# MCB-USI-WM-BN-BM-22-v1_0_0.net
KiCad netlist of a schematic drawn in EAGLE
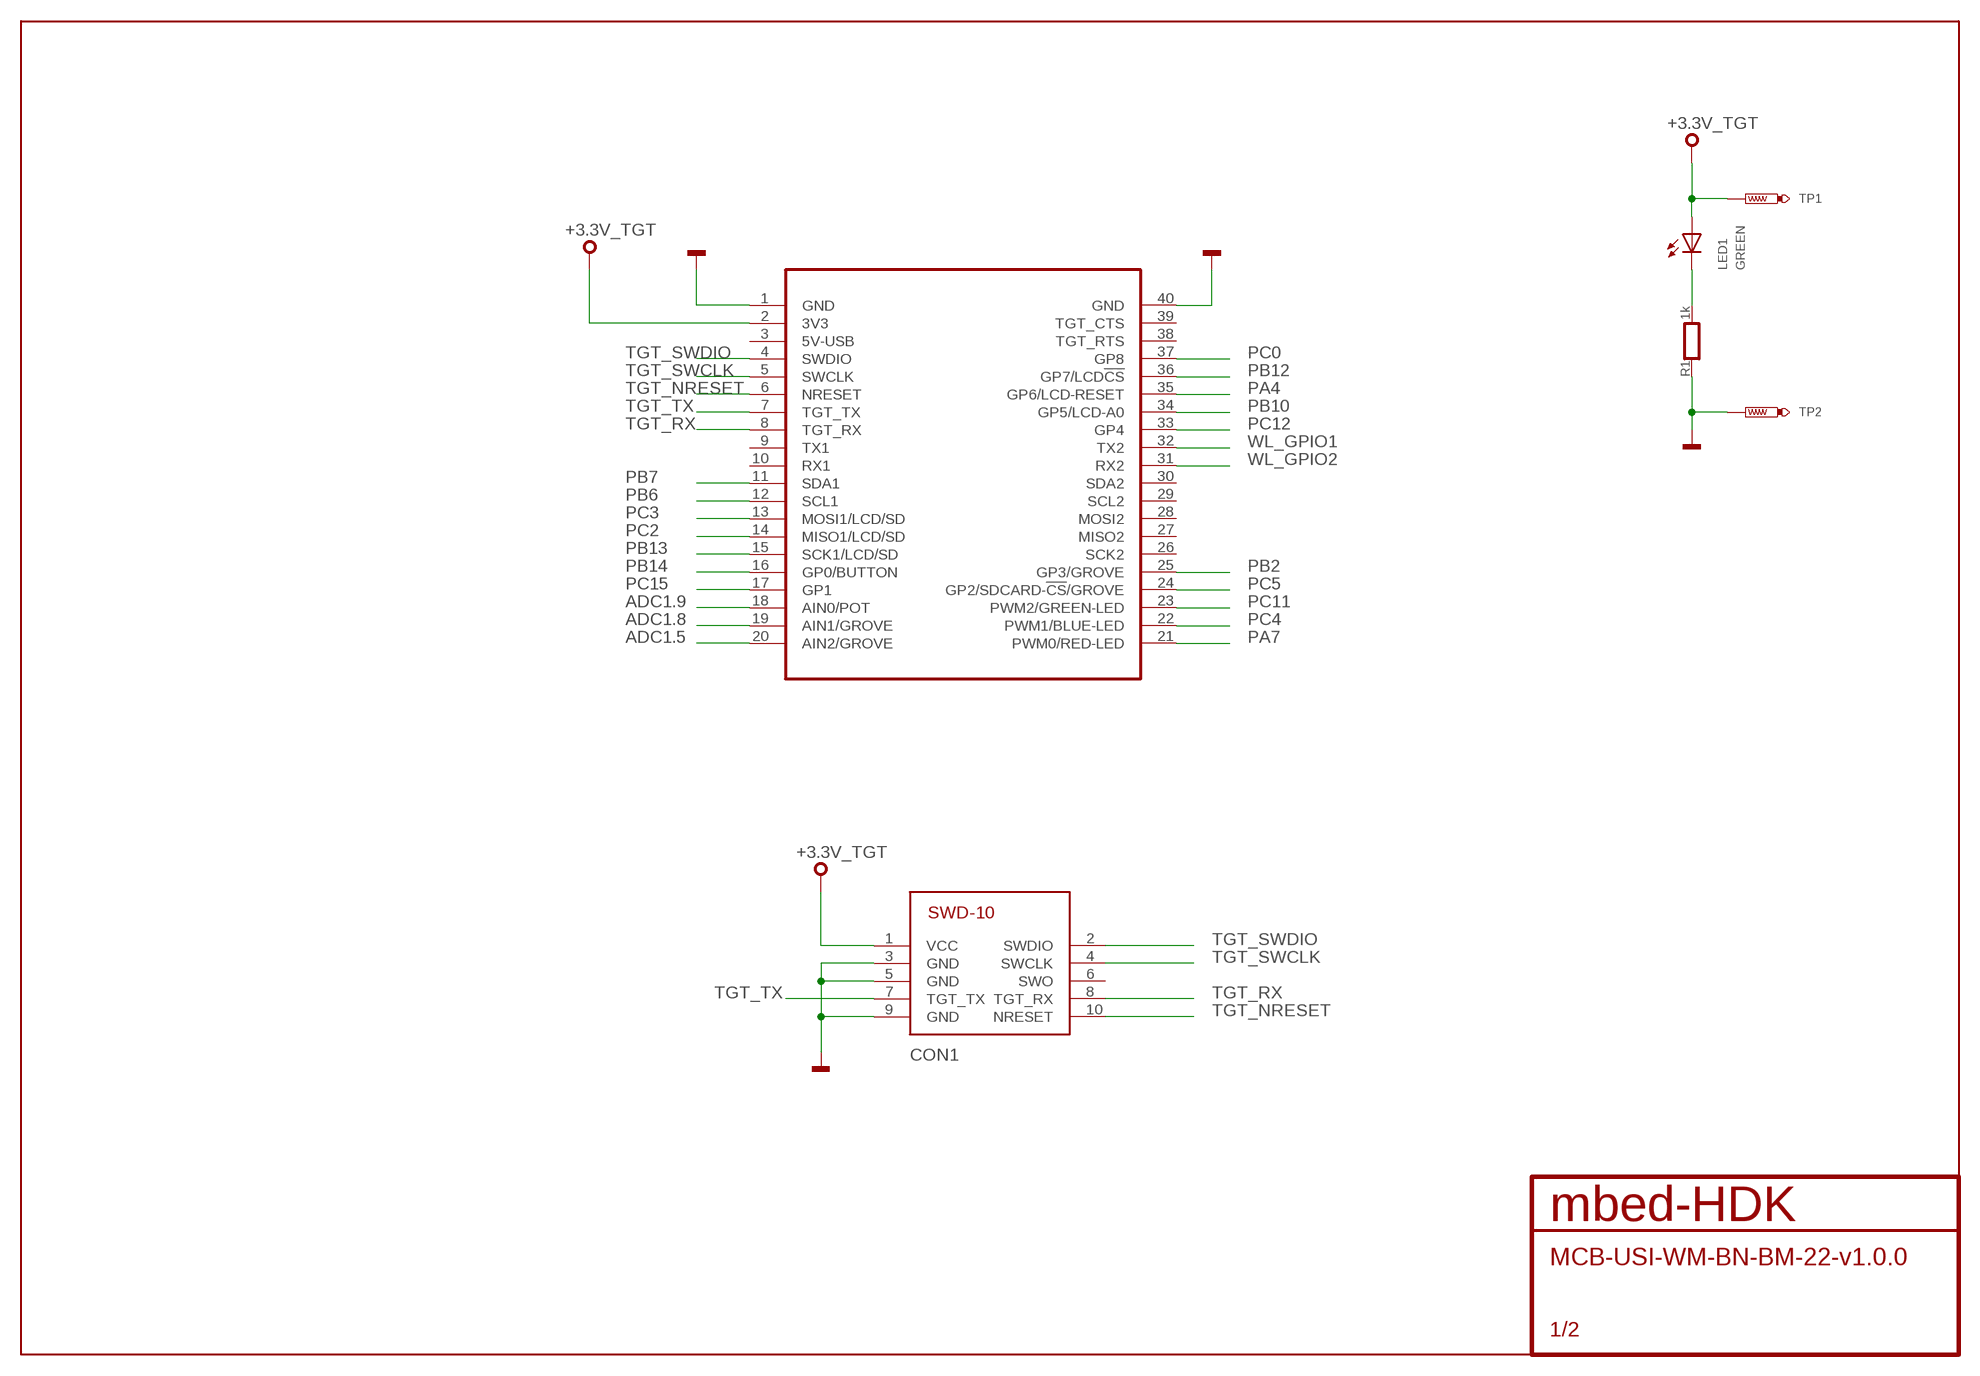
[diagram p0: schematic, sheet 1]
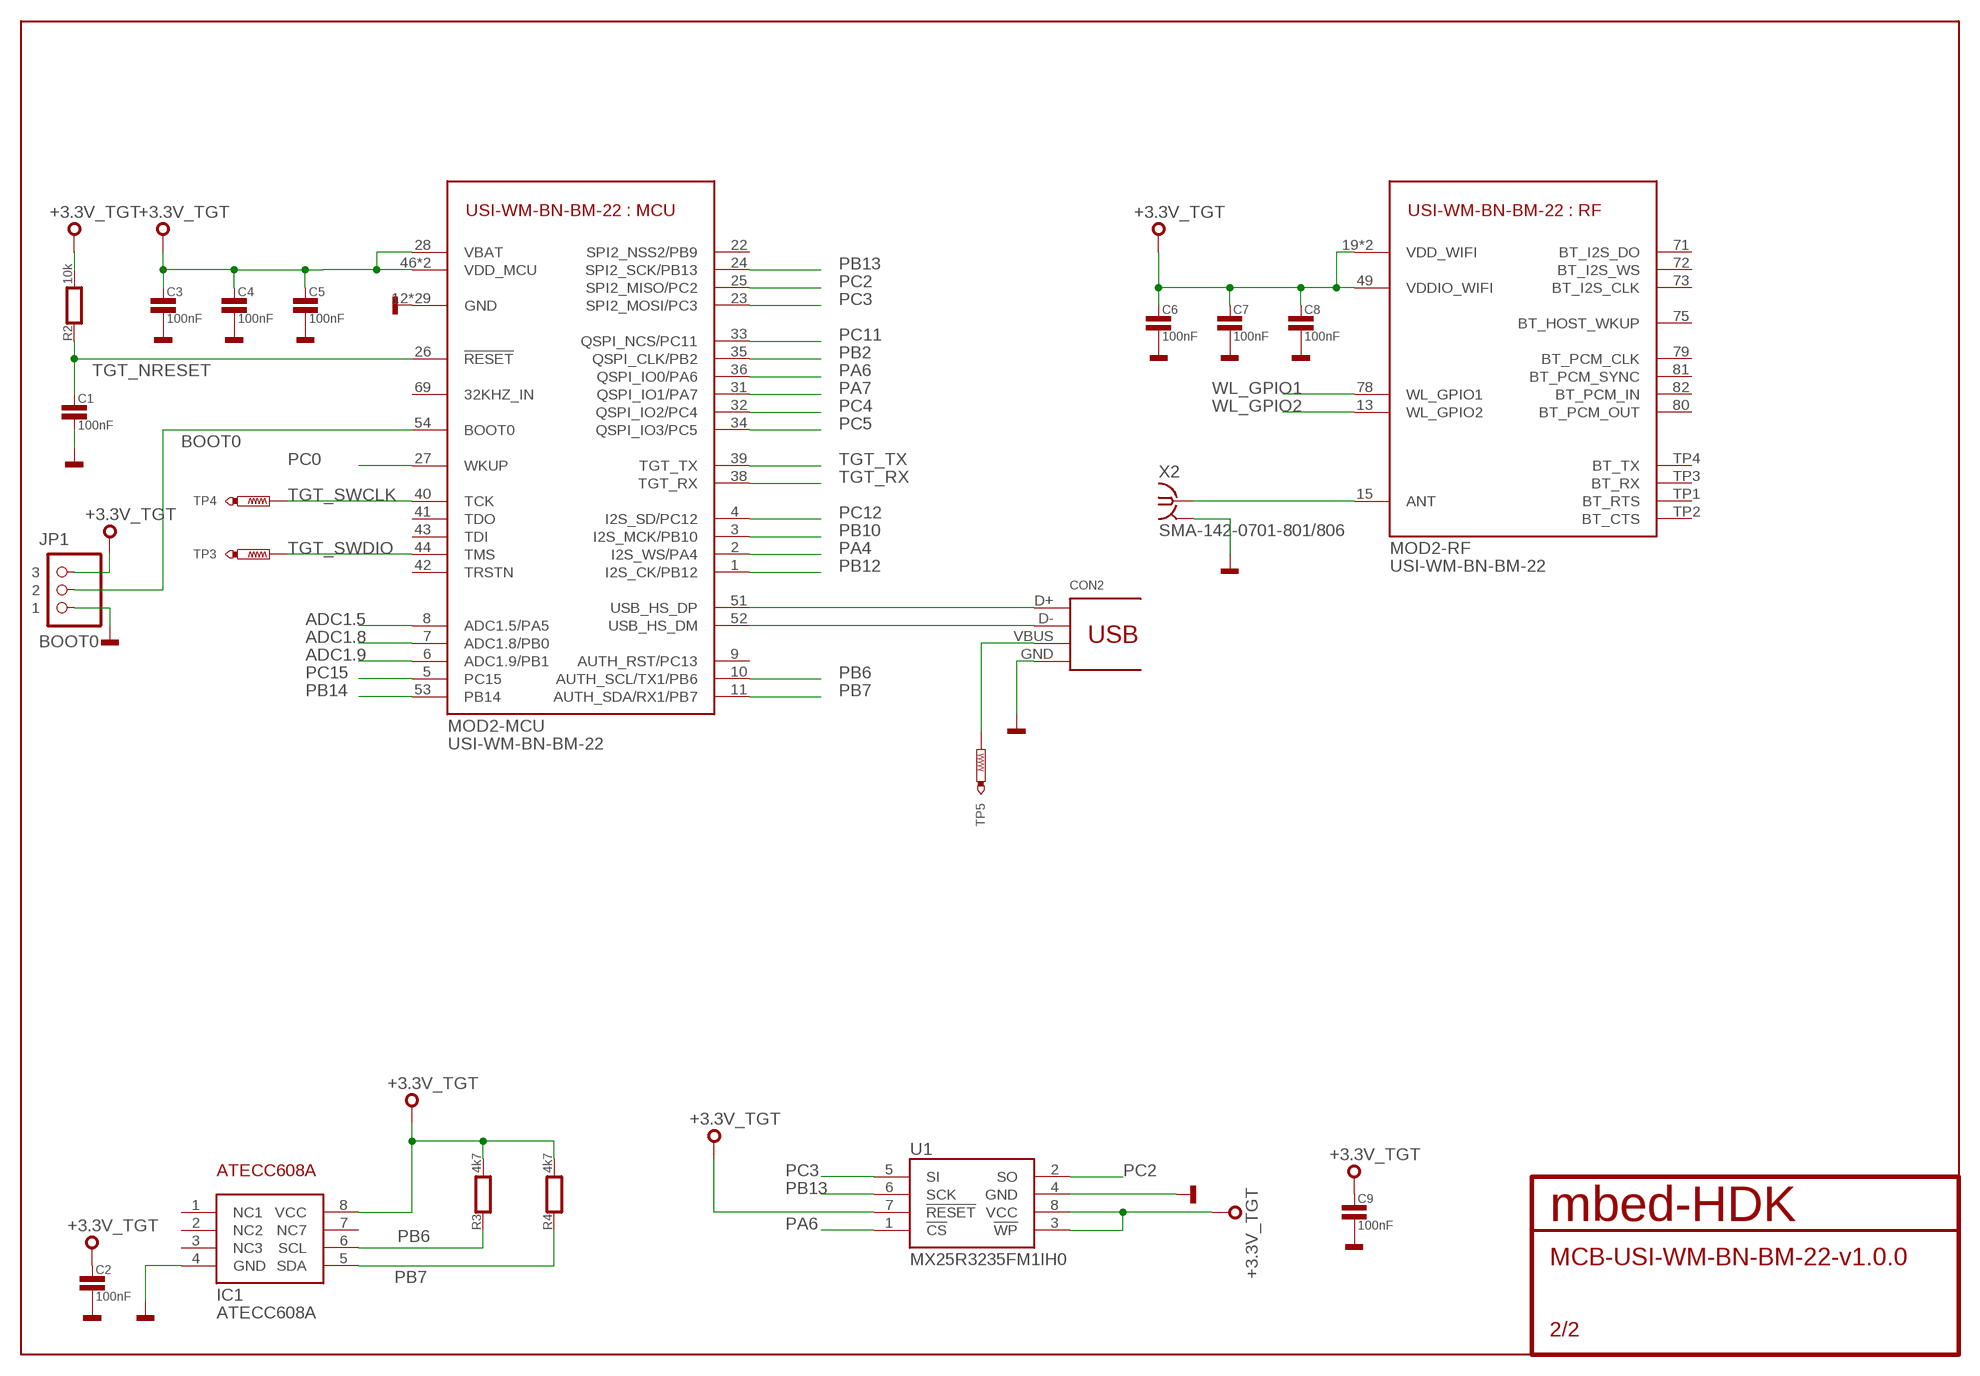
[diagram p1: schematic, sheet 2]

(export (version "E")
  (design (tool "Eeschema 10.0.6"))
  (components
    (comp (ref "CON1")
      (value "SWD-10/TC2050_SMD")
      (footprint "eagle-import:FTSH-105-02")
      (libsource (lib "eagle-import") (part "SWD-10/TC2050_SMD"))
    )
    (comp (ref "LED1")
      (value "GREEN")
      (footprint "eagle-import:CHIPLED_0603")
      (fields (field (name "MF") "Wurth Electronics Inc"))
      (libsource (lib "eagle-import") (part "SMD_LED0603"))
    )
    (comp (ref "MOD1")
      (value "MODULE_DAUGHTER")
      (footprint "eagle-import:MODULE_DAUGHTER")
      (libsource (lib "eagle-import") (part "MODULE_DAUGHTER"))
    )
    (comp (ref "R1")
      (value "1k")
      (footprint "eagle-import:0603")
      (libsource (lib "eagle-import") (part "R0603"))
    )
    (comp (ref "TP1")
      (value "TEST_POINT-50R-PTH")
      (footprint "eagle-import:TP50-PTH")
      (libsource (lib "eagle-import") (part "TEST_POINT-50R-PTH"))
    )
    (comp (ref "TP2")
      (value "TEST_POINT-50R-PTH")
      (footprint "eagle-import:TP50-PTH")
      (libsource (lib "eagle-import") (part "TEST_POINT-50R-PTH"))
    )
    (comp (ref "C1")
      (value "100nF")
      (footprint "eagle-import:0603")
      (libsource (lib "eagle-import") (part "C0603"))
    )
    (comp (ref "C2")
      (value "100nF")
      (footprint "eagle-import:0603")
      (libsource (lib "eagle-import") (part "C0603"))
    )
    (comp (ref "C3")
      (value "100nF")
      (footprint "eagle-import:0603")
      (libsource (lib "eagle-import") (part "C0603"))
    )
    (comp (ref "C4")
      (value "100nF")
      (footprint "eagle-import:0603")
      (libsource (lib "eagle-import") (part "C0603"))
    )
    (comp (ref "C5")
      (value "100nF")
      (footprint "eagle-import:0603")
      (libsource (lib "eagle-import") (part "C0603"))
    )
    (comp (ref "C6")
      (value "100nF")
      (footprint "eagle-import:0603")
      (libsource (lib "eagle-import") (part "C0603"))
    )
    (comp (ref "C7")
      (value "100nF")
      (footprint "eagle-import:0603")
      (libsource (lib "eagle-import") (part "C0603"))
    )
    (comp (ref "C8")
      (value "100nF")
      (footprint "eagle-import:0603")
      (libsource (lib "eagle-import") (part "C0603"))
    )
    (comp (ref "C9")
      (value "100nF")
      (footprint "eagle-import:0603")
      (libsource (lib "eagle-import") (part "C0603"))
    )
    (comp (ref "CON2")
      (value "47346-0001")
      (footprint "eagle-import:USB-MICRO-B-H")
      (fields (field (name "MF") "MOLEX"))
      (libsource (lib "eagle-import") (part "47346-0001"))
    )
    (comp (ref "IC1")
      (value "ATECC608A")
      (footprint "eagle-import:SO8")
      (fields (field (name "MF") "Atmel"))
      (libsource (lib "eagle-import") (part "ATECC608A"))
    )
    (comp (ref "JP1")
      (value "BOOT0")
      (footprint "eagle-import:1X03")
      (libsource (lib "eagle-import") (part "PINHD-1X3"))
    )
    (comp (ref "MOD2")
      (value "USI-WM-BN-BM-22")
      (footprint "eagle-import:USI-WM-BN-BM-22")
      (libsource (lib "eagle-import") (part "USI-WM-BN-BM-22"))
    )
    (comp (ref "R2")
      (value "10k")
      (footprint "eagle-import:0603")
      (libsource (lib "eagle-import") (part "R0603"))
    )
    (comp (ref "R3")
      (value "4k7")
      (footprint "eagle-import:0603")
      (libsource (lib "eagle-import") (part "R0603"))
    )
    (comp (ref "R4")
      (value "4k7")
      (footprint "eagle-import:0603")
      (libsource (lib "eagle-import") (part "R0603"))
    )
    (comp (ref "TP3")
      (value "TEST_POINT-50R-SMD")
      (footprint "eagle-import:TP50-SMD")
      (libsource (lib "eagle-import") (part "TEST_POINT-50R-SMD"))
    )
    (comp (ref "TP4")
      (value "TEST_POINT-50R-SMD")
      (footprint "eagle-import:TP50-SMD")
      (libsource (lib "eagle-import") (part "TEST_POINT-50R-SMD"))
    )
    (comp (ref "TP5")
      (value "TEST_POINT-50R-SMD")
      (footprint "eagle-import:TP50-SMD")
      (libsource (lib "eagle-import") (part "TEST_POINT-50R-SMD"))
    )
    (comp (ref "U1")
      (value "MX25R3235FM1IH0")
      (footprint "eagle-import:SO8")
      (fields (field (name "MF") "Macronix"))
      (libsource (lib "eagle-import") (part "MX25R3235FM1IH0"))
    )
    (comp (ref "X2")
      (value "SMA-142-0701-801/806")
      (footprint "eagle-import:J502-ND-142-0701-801_806")
      (fields (field (name "MF") "JOHNSON COMPONENTS") (field (name "MPN") "142-0701-801"))
      (libsource (lib "eagle-import") (part "SMA-142-0701-801/806"))
    )
  )
  (nets
    (net (code "1") (name "+3.3V_TGT") (class "Default")
      (node (ref "C2") (pin "1") (pinfunction "P$1_1") (pintype "passive"))
      (node (ref "C3") (pin "1") (pinfunction "P$1_1") (pintype "passive"))
      (node (ref "C4") (pin "1") (pinfunction "P$1_1") (pintype "passive"))
      (node (ref "C5") (pin "1") (pinfunction "P$1_1") (pintype "passive"))
      (node (ref "C6") (pin "1") (pinfunction "P$1_1") (pintype "passive"))
      (node (ref "C7") (pin "1") (pinfunction "P$1_1") (pintype "passive"))
      (node (ref "C8") (pin "1") (pinfunction "P$1_1") (pintype "passive"))
      (node (ref "C9") (pin "1") (pinfunction "P$1_1") (pintype "passive"))
      (node (ref "CON1") (pin "1") (pinfunction "VCC_1") (pintype "bidirectional"))
      (node (ref "IC1") (pin "8") (pinfunction "VCC_8") (pintype "bidirectional"))
      (node (ref "JP1") (pin "3") (pinfunction "3_3") (pintype "passive"))
      (node (ref "LED1") (pin "A") (pinfunction "A_A") (pintype "passive"))
      (node (ref "MOD1") (pin "2") (pinfunction "3V3_2") (pintype "bidirectional"))
      (node (ref "MOD2") (pin "19") (pinfunction "VDD_WIFI_19") (pintype "bidirectional"))
      (node (ref "MOD2") (pin "20") (pinfunction "VDD_WIFI_20") (pintype "bidirectional"))
      (node (ref "MOD2") (pin "28") (pinfunction "VBAT_28") (pintype "bidirectional"))
      (node (ref "MOD2") (pin "46") (pinfunction "VDD_MCU_46") (pintype "bidirectional"))
      (node (ref "MOD2") (pin "47") (pinfunction "VDD_MCU_47") (pintype "bidirectional"))
      (node (ref "MOD2") (pin "49") (pinfunction "VDDIO_WIFI_49") (pintype "bidirectional"))
      (node (ref "R2") (pin "2") (pinfunction "P$2_2") (pintype "passive"))
      (node (ref "R3") (pin "2") (pinfunction "P$2_2") (pintype "passive"))
      (node (ref "R4") (pin "2") (pinfunction "P$2_2") (pintype "passive"))
      (node (ref "TP1") (pin "TP") (pinfunction "TP_TP") (pintype "input"))
      (node (ref "U1") (pin "3") (pinfunction "~{WP}_3") (pintype "bidirectional"))
      (node (ref "U1") (pin "7") (pinfunction "~{RESET}_7") (pintype "bidirectional"))
      (node (ref "U1") (pin "8") (pinfunction "VCC_8") (pintype "bidirectional"))
    )
    (net (code "2") (name "ADC1.5") (class "Default")
      (node (ref "MOD1") (pin "20") (pinfunction "AIN2/GROVE_20") (pintype "bidirectional"))
      (node (ref "MOD2") (pin "8") (pinfunction "ADC1.5/PA5_8") (pintype "bidirectional"))
    )
    (net (code "3") (name "ADC1.8") (class "Default")
      (node (ref "MOD1") (pin "19") (pinfunction "AIN1/GROVE_19") (pintype "bidirectional"))
      (node (ref "MOD2") (pin "7") (pinfunction "ADC1.8/PB0_7") (pintype "bidirectional"))
    )
    (net (code "4") (name "ADC1.9") (class "Default")
      (node (ref "MOD1") (pin "18") (pinfunction "AIN0/POT_18") (pintype "bidirectional"))
      (node (ref "MOD2") (pin "6") (pinfunction "ADC1.9/PB1_6") (pintype "bidirectional"))
    )
    (net (code "5") (name "BOOT0") (class "Default")
      (node (ref "JP1") (pin "2") (pinfunction "2_2") (pintype "passive"))
      (node (ref "MOD2") (pin "54") (pinfunction "BOOT0_54") (pintype "bidirectional"))
    )
    (net (code "6") (name "GND") (class "Default")
      (node (ref "C1") (pin "2") (pinfunction "P$2_2") (pintype "passive"))
      (node (ref "C2") (pin "2") (pinfunction "P$2_2") (pintype "passive"))
      (node (ref "C3") (pin "2") (pinfunction "P$2_2") (pintype "passive"))
      (node (ref "C4") (pin "2") (pinfunction "P$2_2") (pintype "passive"))
      (node (ref "C5") (pin "2") (pinfunction "P$2_2") (pintype "passive"))
      (node (ref "C6") (pin "2") (pinfunction "P$2_2") (pintype "passive"))
      (node (ref "C7") (pin "2") (pinfunction "P$2_2") (pintype "passive"))
      (node (ref "C8") (pin "2") (pinfunction "P$2_2") (pintype "passive"))
      (node (ref "C9") (pin "2") (pinfunction "P$2_2") (pintype "passive"))
      (node (ref "CON1") (pin "3") (pinfunction "GND_3") (pintype "bidirectional"))
      (node (ref "CON1") (pin "5") (pinfunction "GND_5") (pintype "bidirectional"))
      (node (ref "CON1") (pin "9") (pinfunction "GND_9") (pintype "bidirectional"))
      (node (ref "CON2") (pin "GND") (pinfunction "GND_GND") (pintype "bidirectional"))
      (node (ref "IC1") (pin "4") (pinfunction "GND_4") (pintype "bidirectional"))
      (node (ref "JP1") (pin "1") (pinfunction "1_1") (pintype "passive"))
      (node (ref "MOD1") (pin "1") (pinfunction "GND_1") (pintype "bidirectional"))
      (node (ref "MOD1") (pin "40") (pinfunction "GND_40") (pintype "bidirectional"))
      (node (ref "MOD2") (pin "12") (pinfunction "GND_12") (pintype "bidirectional"))
      (node (ref "MOD2") (pin "14") (pinfunction "GND_14") (pintype "bidirectional"))
      (node (ref "MOD2") (pin "16") (pinfunction "GND_16") (pintype "bidirectional"))
      (node (ref "MOD2") (pin "17") (pinfunction "GND_17") (pintype "bidirectional"))
      (node (ref "MOD2") (pin "18") (pinfunction "GND_18") (pintype "bidirectional"))
      (node (ref "MOD2") (pin "21") (pinfunction "GND_21") (pintype "bidirectional"))
      (node (ref "MOD2") (pin "29") (pinfunction "GND_29") (pintype "bidirectional"))
      (node (ref "MOD2") (pin "30") (pinfunction "GND_30") (pintype "bidirectional"))
      (node (ref "MOD2") (pin "37") (pinfunction "GND_37") (pintype "bidirectional"))
      (node (ref "MOD2") (pin "45") (pinfunction "GND_45") (pintype "bidirectional"))
      (node (ref "MOD2") (pin "48") (pinfunction "GND_48") (pintype "bidirectional"))
      (node (ref "MOD2") (pin "50") (pinfunction "GND_50") (pintype "bidirectional"))
      (node (ref "MOD2") (pin "55") (pinfunction "GND_55") (pintype "bidirectional"))
      (node (ref "MOD2") (pin "56") (pinfunction "GND_56") (pintype "bidirectional"))
      (node (ref "MOD2") (pin "57") (pinfunction "GND_57") (pintype "bidirectional"))
      (node (ref "MOD2") (pin "58") (pinfunction "GND_58") (pintype "bidirectional"))
      (node (ref "MOD2") (pin "59") (pinfunction "GND_59") (pintype "bidirectional"))
      (node (ref "MOD2") (pin "60") (pinfunction "GND_60") (pintype "bidirectional"))
      (node (ref "MOD2") (pin "61") (pinfunction "GND_61") (pintype "bidirectional"))
      (node (ref "MOD2") (pin "62") (pinfunction "GND_62") (pintype "bidirectional"))
      (node (ref "MOD2") (pin "63") (pinfunction "GND_63") (pintype "bidirectional"))
      (node (ref "MOD2") (pin "64") (pinfunction "GND_64") (pintype "bidirectional"))
      (node (ref "MOD2") (pin "65") (pinfunction "GND_65") (pintype "bidirectional"))
      (node (ref "MOD2") (pin "66") (pinfunction "GND_66") (pintype "bidirectional"))
      (node (ref "MOD2") (pin "67") (pinfunction "GND_67") (pintype "bidirectional"))
      (node (ref "MOD2") (pin "68") (pinfunction "GND_68") (pintype "bidirectional"))
      (node (ref "MOD2") (pin "70") (pinfunction "GND_70") (pintype "bidirectional"))
      (node (ref "MOD2") (pin "74") (pinfunction "GND_74") (pintype "bidirectional"))
      (node (ref "MOD2") (pin "83") (pinfunction "GND_83") (pintype "bidirectional"))
      (node (ref "R1") (pin "1") (pinfunction "P$1_1") (pintype "passive"))
      (node (ref "TP2") (pin "TP") (pinfunction "TP_TP") (pintype "input"))
      (node (ref "U1") (pin "4") (pinfunction "GND_4") (pintype "bidirectional"))
      (node (ref "X2") (pin "G@1") (pinfunction "2_G@1") (pintype "passive"))
      (node (ref "X2") (pin "G@2") (pinfunction "2_G@2") (pintype "passive"))
      (node (ref "X2") (pin "G@3") (pinfunction "2_G@3") (pintype "passive"))
      (node (ref "X2") (pin "G@4") (pinfunction "2_G@4") (pintype "passive"))
    )
    (net (code "7") (name "Net-(CON2-PadVBUS)") (class "Default")
      (node (ref "CON2") (pin "VBUS") (pinfunction "VBUS_VBUS") (pintype "bidirectional"))
      (node (ref "TP5") (pin "TP") (pinfunction "TP_TP") (pintype "input"))
    )
    (net (code "8") (name "Net-(MOD2A-USB_HS_DM)") (class "Default")
      (node (ref "CON2") (pin "D-") (pinfunction "D-_D-") (pintype "bidirectional"))
      (node (ref "MOD2") (pin "52") (pinfunction "USB_HS_DM_52") (pintype "bidirectional"))
    )
    (net (code "9") (name "Net-(MOD2A-USB_HS_DP)") (class "Default")
      (node (ref "CON2") (pin "D+") (pinfunction "D+_D+") (pintype "bidirectional"))
      (node (ref "MOD2") (pin "51") (pinfunction "USB_HS_DP_51") (pintype "bidirectional"))
    )
    (net (code "10") (name "Net-(MOD2B-ANT)") (class "Default")
      (node (ref "MOD2") (pin "15") (pinfunction "ANT_15") (pintype "bidirectional"))
      (node (ref "X2") (pin "1") (pinfunction "1_1") (pintype "passive"))
    )
    (net (code "11") (name "Net-(R1-P$2)") (class "Default")
      (node (ref "LED1") (pin "C") (pinfunction "C_C") (pintype "passive"))
      (node (ref "R1") (pin "2") (pinfunction "P$2_2") (pintype "passive"))
    )
    (net (code "12") (name "PA4") (class "Default")
      (node (ref "MOD1") (pin "35") (pinfunction "GP6/LCD-RESET_35") (pintype "bidirectional"))
      (node (ref "MOD2") (pin "2") (pinfunction "I2S_WS/PA4_2") (pintype "bidirectional"))
    )
    (net (code "13") (name "PA6") (class "Default")
      (node (ref "MOD2") (pin "36") (pinfunction "QSPI_IO0/PA6_36") (pintype "bidirectional"))
      (node (ref "U1") (pin "1") (pinfunction "~{CS}_1") (pintype "bidirectional"))
    )
    (net (code "14") (name "PA7") (class "Default")
      (node (ref "MOD1") (pin "21") (pinfunction "PWM0/RED-LED_21") (pintype "bidirectional"))
      (node (ref "MOD2") (pin "31") (pinfunction "QSPI_IO1/PA7_31") (pintype "bidirectional"))
    )
    (net (code "15") (name "PB2") (class "Default")
      (node (ref "MOD1") (pin "25") (pinfunction "GP3/GROVE_25") (pintype "bidirectional"))
      (node (ref "MOD2") (pin "35") (pinfunction "QSPI_CLK/PB2_35") (pintype "bidirectional"))
    )
    (net (code "16") (name "PB6") (class "Default")
      (node (ref "IC1") (pin "6") (pinfunction "SCL_6") (pintype "bidirectional"))
      (node (ref "MOD1") (pin "12") (pinfunction "SCL1_12") (pintype "bidirectional"))
      (node (ref "MOD2") (pin "10") (pinfunction "AUTH_SCL/TX1/PB6_10") (pintype "bidirectional"))
      (node (ref "R3") (pin "1") (pinfunction "P$1_1") (pintype "passive"))
    )
    (net (code "17") (name "PB7") (class "Default")
      (node (ref "IC1") (pin "5") (pinfunction "SDA_5") (pintype "bidirectional"))
      (node (ref "MOD1") (pin "11") (pinfunction "SDA1_11") (pintype "bidirectional"))
      (node (ref "MOD2") (pin "11") (pinfunction "AUTH_SDA/RX1/PB7_11") (pintype "bidirectional"))
      (node (ref "R4") (pin "1") (pinfunction "P$1_1") (pintype "passive"))
    )
    (net (code "18") (name "PB10") (class "Default")
      (node (ref "MOD1") (pin "34") (pinfunction "GP5/LCD-A0_34") (pintype "bidirectional"))
      (node (ref "MOD2") (pin "3") (pinfunction "I2S_MCK/PB10_3") (pintype "bidirectional"))
    )
    (net (code "19") (name "PB12") (class "Default")
      (node (ref "MOD1") (pin "36") (pinfunction "GP7/LCD~{CS}_36") (pintype "bidirectional"))
      (node (ref "MOD2") (pin "1") (pinfunction "I2S_CK/PB12_1") (pintype "bidirectional"))
    )
    (net (code "20") (name "PB13") (class "Default")
      (node (ref "MOD1") (pin "15") (pinfunction "SCK1/LCD/SD_15") (pintype "bidirectional"))
      (node (ref "MOD2") (pin "24") (pinfunction "SPI2_SCK/PB13_24") (pintype "bidirectional"))
      (node (ref "U1") (pin "6") (pinfunction "SCK_6") (pintype "bidirectional"))
    )
    (net (code "21") (name "PB14") (class "Default")
      (node (ref "MOD1") (pin "16") (pinfunction "GP0/BUTTON_16") (pintype "bidirectional"))
      (node (ref "MOD2") (pin "53") (pinfunction "PB14_53") (pintype "bidirectional"))
    )
    (net (code "22") (name "PC0") (class "Default")
      (node (ref "MOD1") (pin "37") (pinfunction "GP8_37") (pintype "bidirectional"))
      (node (ref "MOD2") (pin "27") (pinfunction "WKUP_27") (pintype "bidirectional"))
    )
    (net (code "23") (name "PC2") (class "Default")
      (node (ref "MOD1") (pin "14") (pinfunction "MISO1/LCD/SD_14") (pintype "bidirectional"))
      (node (ref "MOD2") (pin "25") (pinfunction "SPI2_MISO/PC2_25") (pintype "bidirectional"))
      (node (ref "U1") (pin "2") (pinfunction "SO_2") (pintype "bidirectional"))
    )
    (net (code "24") (name "PC3") (class "Default")
      (node (ref "MOD1") (pin "13") (pinfunction "MOSI1/LCD/SD_13") (pintype "bidirectional"))
      (node (ref "MOD2") (pin "23") (pinfunction "SPI2_MOSI/PC3_23") (pintype "bidirectional"))
      (node (ref "U1") (pin "5") (pinfunction "SI_5") (pintype "bidirectional"))
    )
    (net (code "25") (name "PC4") (class "Default")
      (node (ref "MOD1") (pin "22") (pinfunction "PWM1/BLUE-LED_22") (pintype "bidirectional"))
      (node (ref "MOD2") (pin "32") (pinfunction "QSPI_IO2/PC4_32") (pintype "bidirectional"))
    )
    (net (code "26") (name "PC5") (class "Default")
      (node (ref "MOD1") (pin "24") (pinfunction "GP2/SDCARD-~{CS}/GROVE_24") (pintype "bidirectional"))
      (node (ref "MOD2") (pin "34") (pinfunction "QSPI_IO3/PC5_34") (pintype "bidirectional"))
    )
    (net (code "27") (name "PC11") (class "Default")
      (node (ref "MOD1") (pin "23") (pinfunction "PWM2/GREEN-LED_23") (pintype "bidirectional"))
      (node (ref "MOD2") (pin "33") (pinfunction "QSPI_NCS/PC11_33") (pintype "bidirectional"))
    )
    (net (code "28") (name "PC12") (class "Default")
      (node (ref "MOD1") (pin "33") (pinfunction "GP4_33") (pintype "bidirectional"))
      (node (ref "MOD2") (pin "4") (pinfunction "I2S_SD/PC12_4") (pintype "bidirectional"))
    )
    (net (code "29") (name "PC15") (class "Default")
      (node (ref "MOD1") (pin "17") (pinfunction "GP1_17") (pintype "bidirectional"))
      (node (ref "MOD2") (pin "5") (pinfunction "PC15_5") (pintype "bidirectional"))
    )
    (net (code "30") (name "TGT_NRESET") (class "Default")
      (node (ref "C1") (pin "1") (pinfunction "P$1_1") (pintype "passive"))
      (node (ref "CON1") (pin "10") (pinfunction "NRESET_10") (pintype "bidirectional"))
      (node (ref "MOD1") (pin "6") (pinfunction "NRESET_6") (pintype "bidirectional"))
      (node (ref "MOD2") (pin "26") (pinfunction "~{RESET}_26") (pintype "bidirectional"))
      (node (ref "R2") (pin "1") (pinfunction "P$1_1") (pintype "passive"))
    )
    (net (code "31") (name "TGT_RX") (class "Default")
      (node (ref "CON1") (pin "8") (pinfunction "TGT_RX_8") (pintype "bidirectional"))
      (node (ref "MOD1") (pin "8") (pinfunction "TGT_RX_8") (pintype "bidirectional"))
      (node (ref "MOD2") (pin "38") (pinfunction "TGT_RX_38") (pintype "bidirectional"))
    )
    (net (code "32") (name "TGT_SWCLK") (class "Default")
      (node (ref "CON1") (pin "4") (pinfunction "SWCLK_4") (pintype "bidirectional"))
      (node (ref "MOD1") (pin "5") (pinfunction "SWCLK_5") (pintype "bidirectional"))
      (node (ref "MOD2") (pin "40") (pinfunction "TCK_40") (pintype "bidirectional"))
      (node (ref "TP4") (pin "TP") (pinfunction "TP_TP") (pintype "input"))
    )
    (net (code "33") (name "TGT_SWDIO") (class "Default")
      (node (ref "CON1") (pin "2") (pinfunction "SWDIO_2") (pintype "bidirectional"))
      (node (ref "MOD1") (pin "4") (pinfunction "SWDIO_4") (pintype "bidirectional"))
      (node (ref "MOD2") (pin "44") (pinfunction "TMS_44") (pintype "bidirectional"))
      (node (ref "TP3") (pin "TP") (pinfunction "TP_TP") (pintype "input"))
    )
    (net (code "34") (name "TGT_TX") (class "Default")
      (node (ref "CON1") (pin "7") (pinfunction "TGT_TX_7") (pintype "bidirectional"))
      (node (ref "MOD1") (pin "7") (pinfunction "TGT_TX_7") (pintype "bidirectional"))
      (node (ref "MOD2") (pin "39") (pinfunction "TGT_TX_39") (pintype "bidirectional"))
    )
    (net (code "35") (name "WL_GPIO1") (class "Default")
      (node (ref "MOD1") (pin "32") (pinfunction "TX2_32") (pintype "bidirectional"))
      (node (ref "MOD2") (pin "78") (pinfunction "WL_GPIO1_78") (pintype "bidirectional"))
    )
    (net (code "36") (name "WL_GPIO2") (class "Default")
      (node (ref "MOD1") (pin "31") (pinfunction "RX2_31") (pintype "bidirectional"))
      (node (ref "MOD2") (pin "13") (pinfunction "WL_GPIO2_13") (pintype "bidirectional"))
    )
    (net (code "37") (name "unconnected-(CON1-SWO-Pad6)") (class "Default")
      (node (ref "CON1") (pin "6") (pinfunction "SWO_6") (pintype "bidirectional"))
    )
    (net (code "38") (name "unconnected-(IC1-NC1-Pad1)") (class "Default")
      (node (ref "IC1") (pin "1") (pinfunction "NC1_1") (pintype "bidirectional"))
    )
    (net (code "39") (name "unconnected-(IC1-NC2-Pad2)") (class "Default")
      (node (ref "IC1") (pin "2") (pinfunction "NC2_2") (pintype "bidirectional"))
    )
    (net (code "40") (name "unconnected-(IC1-NC3-Pad3)") (class "Default")
      (node (ref "IC1") (pin "3") (pinfunction "NC3_3") (pintype "bidirectional"))
    )
    (net (code "41") (name "unconnected-(IC1-NC7-Pad7)") (class "Default")
      (node (ref "IC1") (pin "7") (pinfunction "NC7_7") (pintype "bidirectional"))
    )
    (net (code "42") (name "unconnected-(MOD1-5V-USB-Pad3)") (class "Default")
      (node (ref "MOD1") (pin "3") (pinfunction "5V-USB_3") (pintype "bidirectional"))
    )
    (net (code "43") (name "unconnected-(MOD1-MISO2-Pad27)") (class "Default")
      (node (ref "MOD1") (pin "27") (pinfunction "MISO2_27") (pintype "bidirectional"))
    )
    (net (code "44") (name "unconnected-(MOD1-MOSI2-Pad28)") (class "Default")
      (node (ref "MOD1") (pin "28") (pinfunction "MOSI2_28") (pintype "bidirectional"))
    )
    (net (code "45") (name "unconnected-(MOD1-RX1-Pad10)") (class "Default")
      (node (ref "MOD1") (pin "10") (pinfunction "RX1_10") (pintype "bidirectional"))
    )
    (net (code "46") (name "unconnected-(MOD1-SCK2-Pad26)") (class "Default")
      (node (ref "MOD1") (pin "26") (pinfunction "SCK2_26") (pintype "bidirectional"))
    )
    (net (code "47") (name "unconnected-(MOD1-SCL2-Pad29)") (class "Default")
      (node (ref "MOD1") (pin "29") (pinfunction "SCL2_29") (pintype "bidirectional"))
    )
    (net (code "48") (name "unconnected-(MOD1-SDA2-Pad30)") (class "Default")
      (node (ref "MOD1") (pin "30") (pinfunction "SDA2_30") (pintype "bidirectional"))
    )
    (net (code "49") (name "unconnected-(MOD1-TGT_CTS-Pad39)") (class "Default")
      (node (ref "MOD1") (pin "39") (pinfunction "TGT_CTS_39") (pintype "bidirectional"))
    )
    (net (code "50") (name "unconnected-(MOD1-TGT_RTS-Pad38)") (class "Default")
      (node (ref "MOD1") (pin "38") (pinfunction "TGT_RTS_38") (pintype "bidirectional"))
    )
    (net (code "51") (name "unconnected-(MOD1-TX1-Pad9)") (class "Default")
      (node (ref "MOD1") (pin "9") (pinfunction "TX1_9") (pintype "bidirectional"))
    )
    (net (code "52") (name "unconnected-(MOD2A-32KHZ_IN-Pad69)") (class "Default")
      (node (ref "MOD2") (pin "69") (pinfunction "32KHZ_IN_69") (pintype "bidirectional"))
    )
    (net (code "53") (name "unconnected-(MOD2A-AUTH_RST{slash}PC13-Pad9)") (class "Default")
      (node (ref "MOD2") (pin "9") (pinfunction "AUTH_RST/PC13_9") (pintype "bidirectional"))
    )
    (net (code "54") (name "unconnected-(MOD2A-SPI2_NSS2{slash}PB9-Pad22)") (class "Default")
      (node (ref "MOD2") (pin "22") (pinfunction "SPI2_NSS2/PB9_22") (pintype "bidirectional"))
    )
    (net (code "55") (name "unconnected-(MOD2A-TDI-Pad43)") (class "Default")
      (node (ref "MOD2") (pin "43") (pinfunction "TDI_43") (pintype "bidirectional"))
    )
    (net (code "56") (name "unconnected-(MOD2A-TDO-Pad41)") (class "Default")
      (node (ref "MOD2") (pin "41") (pinfunction "TDO_41") (pintype "bidirectional"))
    )
    (net (code "57") (name "unconnected-(MOD2A-TRSTN-Pad42)") (class "Default")
      (node (ref "MOD2") (pin "42") (pinfunction "TRSTN_42") (pintype "bidirectional"))
    )
    (net (code "58") (name "unconnected-(MOD2B-BT_CTS-PadTP2)") (class "Default")
      (node (ref "MOD2") (pin "TP2") (pinfunction "BT_CTS_TP2") (pintype "bidirectional"))
    )
    (net (code "59") (name "unconnected-(MOD2B-BT_HOST_WKUP-Pad75)") (class "Default")
      (node (ref "MOD2") (pin "75") (pinfunction "BT_HOST_WKUP_75") (pintype "bidirectional"))
    )
    (net (code "60") (name "unconnected-(MOD2B-BT_I2S_CLK-Pad73)") (class "Default")
      (node (ref "MOD2") (pin "73") (pinfunction "BT_I2S_CLK_73") (pintype "bidirectional"))
    )
    (net (code "61") (name "unconnected-(MOD2B-BT_I2S_DO-Pad71)") (class "Default")
      (node (ref "MOD2") (pin "71") (pinfunction "BT_I2S_DO_71") (pintype "bidirectional"))
    )
    (net (code "62") (name "unconnected-(MOD2B-BT_I2S_WS-Pad72)") (class "Default")
      (node (ref "MOD2") (pin "72") (pinfunction "BT_I2S_WS_72") (pintype "bidirectional"))
    )
    (net (code "63") (name "unconnected-(MOD2B-BT_PCM_CLK-Pad79)") (class "Default")
      (node (ref "MOD2") (pin "79") (pinfunction "BT_PCM_CLK_79") (pintype "bidirectional"))
    )
    (net (code "64") (name "unconnected-(MOD2B-BT_PCM_IN-Pad82)") (class "Default")
      (node (ref "MOD2") (pin "82") (pinfunction "BT_PCM_IN_82") (pintype "bidirectional"))
    )
    (net (code "65") (name "unconnected-(MOD2B-BT_PCM_OUT-Pad80)") (class "Default")
      (node (ref "MOD2") (pin "80") (pinfunction "BT_PCM_OUT_80") (pintype "bidirectional"))
    )
    (net (code "66") (name "unconnected-(MOD2B-BT_PCM_SYNC-Pad81)") (class "Default")
      (node (ref "MOD2") (pin "81") (pinfunction "BT_PCM_SYNC_81") (pintype "bidirectional"))
    )
    (net (code "67") (name "unconnected-(MOD2B-BT_RTS-PadTP1)") (class "Default")
      (node (ref "MOD2") (pin "TP1") (pinfunction "BT_RTS_TP1") (pintype "bidirectional"))
    )
    (net (code "68") (name "unconnected-(MOD2B-BT_RX-PadTP3)") (class "Default")
      (node (ref "MOD2") (pin "TP3") (pinfunction "BT_RX_TP3") (pintype "bidirectional"))
    )
    (net (code "69") (name "unconnected-(MOD2B-BT_TX-PadTP4)") (class "Default")
      (node (ref "MOD2") (pin "TP4") (pinfunction "BT_TX_TP4") (pintype "bidirectional"))
    )
  )
)
